# SCH_High_Voltage_Multipler_2022-07-10.net
KiCad netlist of a schematic drawn in EasyEDA
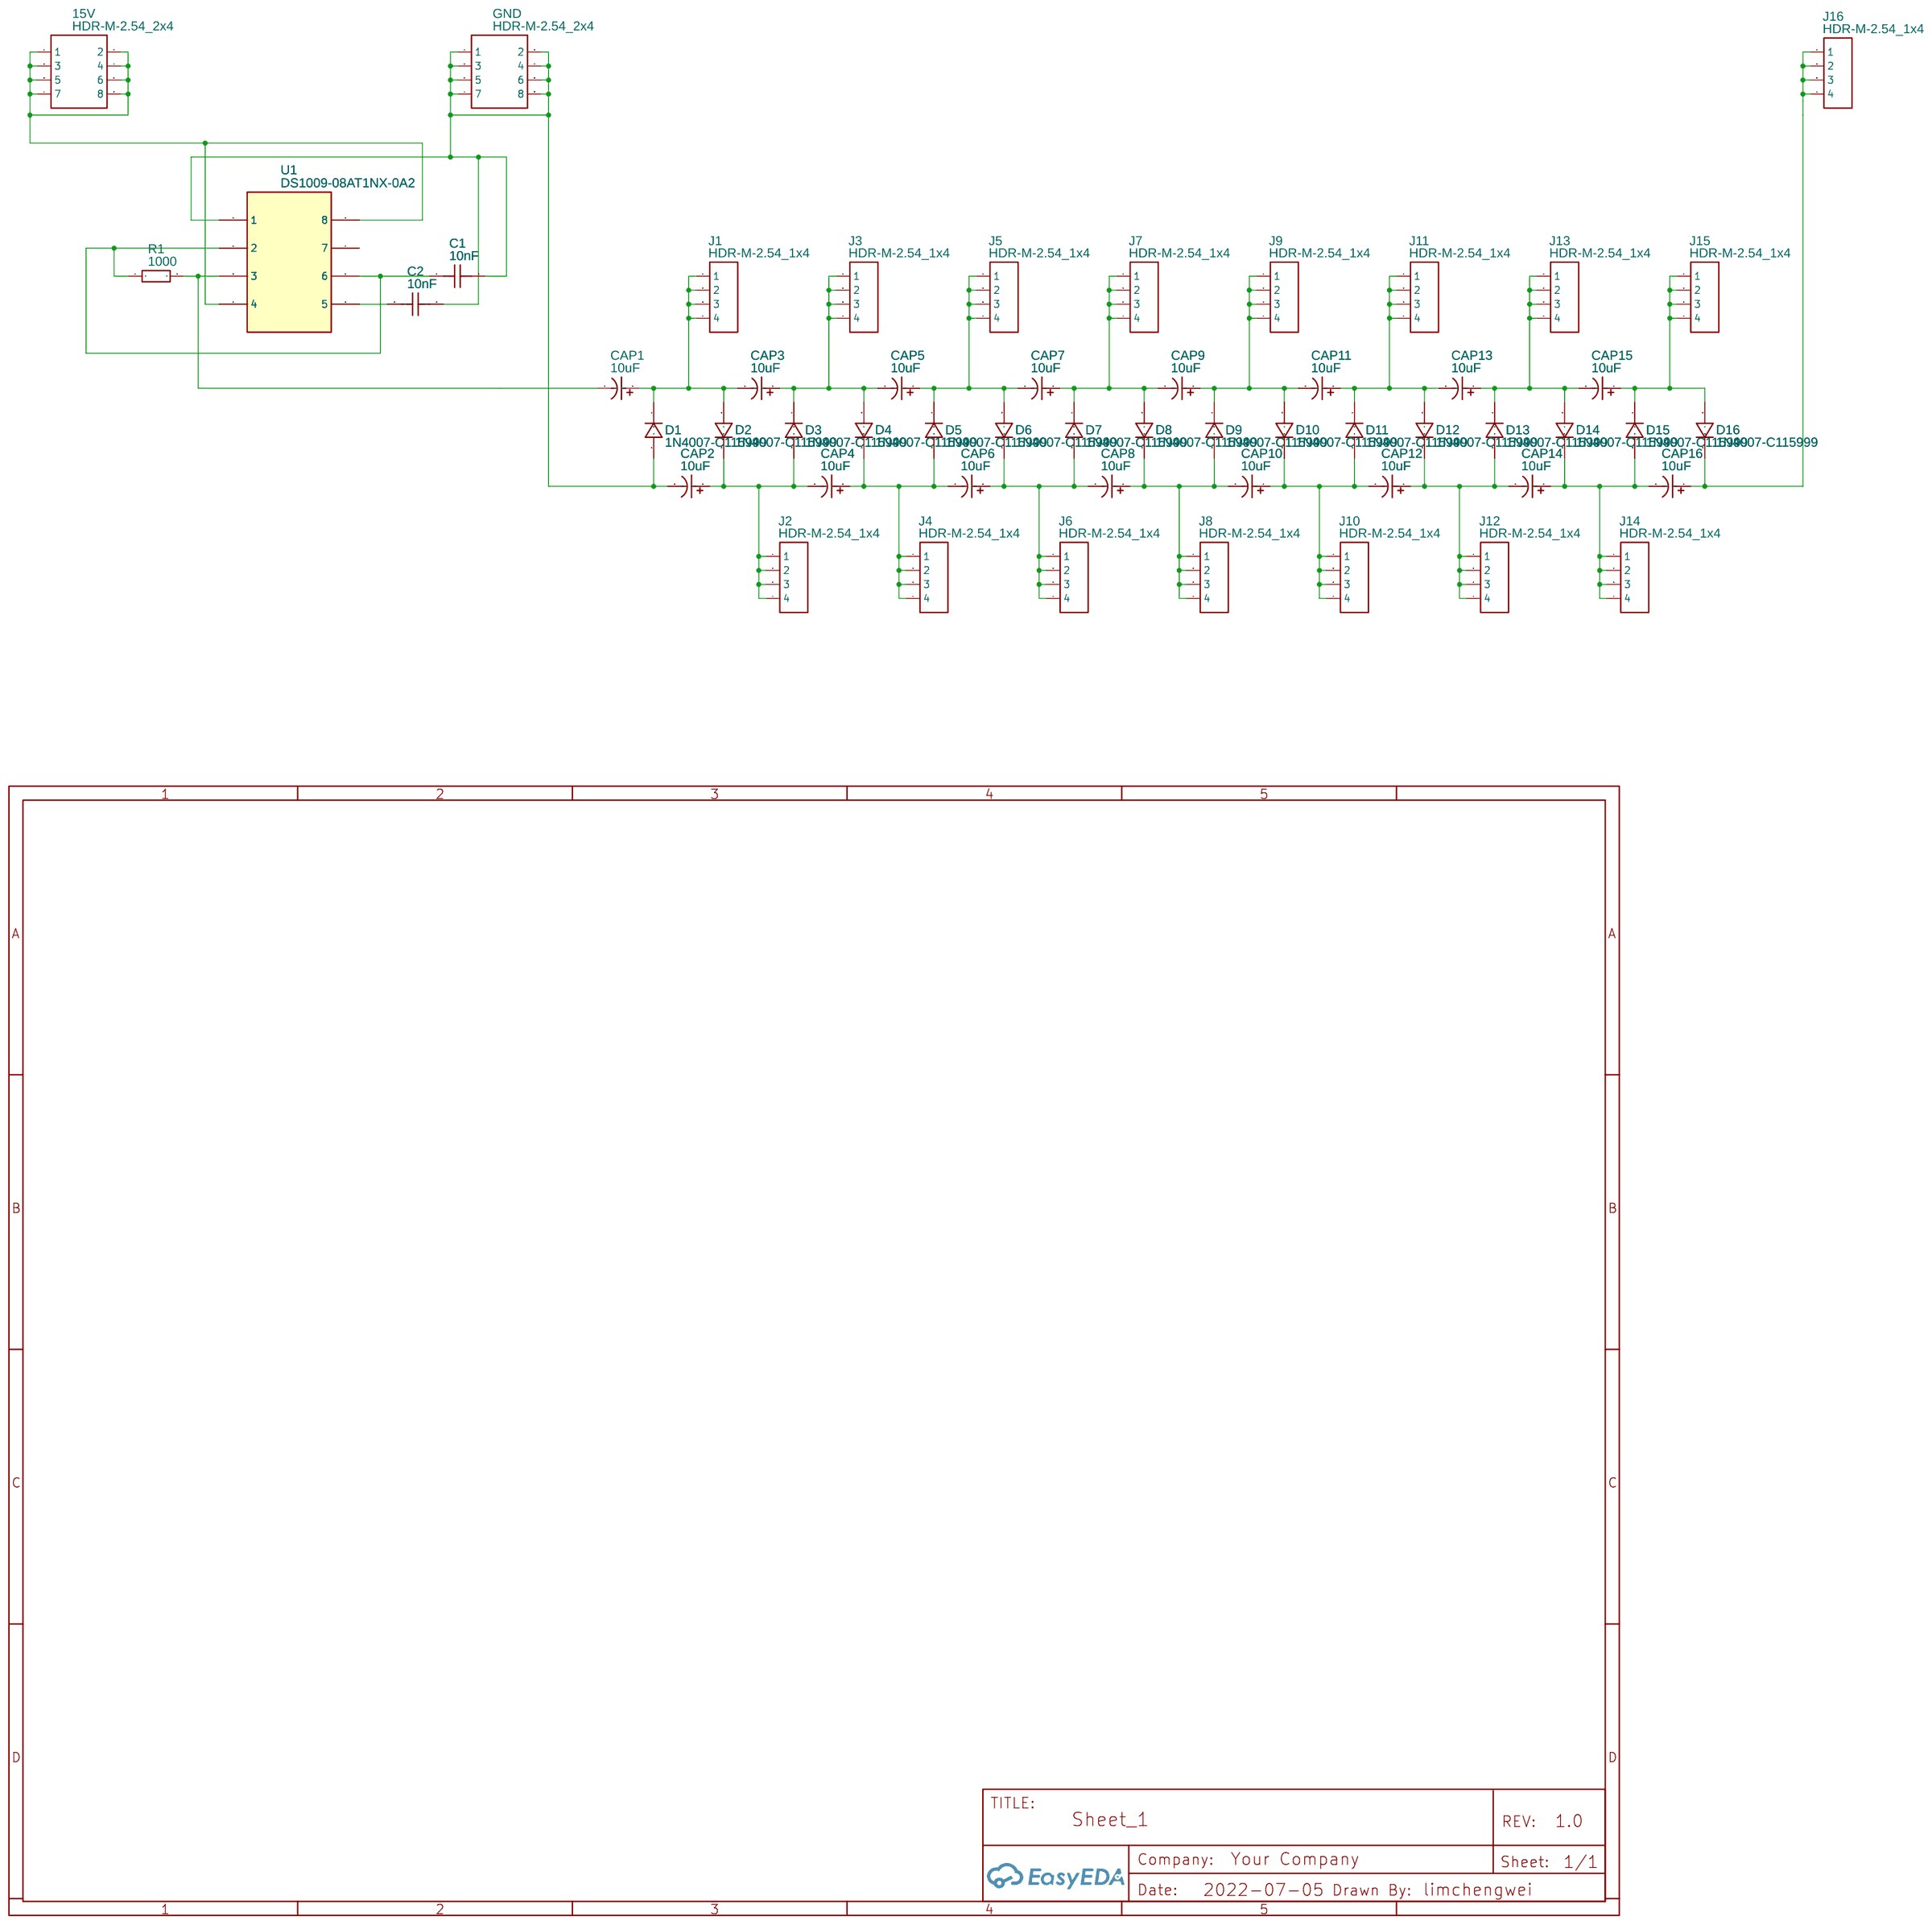
[diagram p0: schematic sheet]

(export (version "E")
  (design (tool "Eeschema 10.0.6"))
  (components
    (comp (ref "15V")
      (value "HDR-M-2.54_2x4")
      (fields (field (name "BOM_Supplier Part") "C58363"))
      (libsource (lib "") (part "HDR-M-2.54_2x4"))
    )
    (comp (ref "C1")
      (value "10nF")
      (fields
        (field (name "BOM_Manufacturer Part") "CC1H103MC76DB45A30S8")
        (field (name "BOM_Supplier Part") "C377837")
      )
      (libsource (lib "") (part "CC1H103MC76DB45A30S8"))
    )
    (comp (ref "C2")
      (value "10nF")
      (fields
        (field (name "BOM_Manufacturer Part") "CC1H103MC76DB45A30S8")
        (field (name "BOM_Supplier Part") "C377837")
      )
      (libsource (lib "") (part "CC1H103MC76DB45A30S8"))
    )
    (comp (ref "CAP1")
      (value "10uF")
      (fields
        (field (name "BOM_Manufacturer Part") "RL1E100MC110A00CV0")
        (field (name "BOM_Supplier Part") "C216293")
      )
      (libsource (lib "") (part "RL1E100MC110A00CV0"))
    )
    (comp (ref "CAP2")
      (value "10uF")
      (fields
        (field (name "BOM_Manufacturer Part") "RL1E100MC110A00CV0")
        (field (name "BOM_Supplier Part") "C216293")
      )
      (libsource (lib "") (part "RL1E100MC110A00CV0"))
    )
    (comp (ref "CAP3")
      (value "10uF")
      (fields
        (field (name "BOM_Manufacturer Part") "RL1E100MC110A00CV0")
        (field (name "BOM_Supplier Part") "C216293")
      )
      (libsource (lib "") (part "RL1E100MC110A00CV0"))
    )
    (comp (ref "CAP4")
      (value "10uF")
      (fields
        (field (name "BOM_Manufacturer Part") "RL1E100MC110A00CV0")
        (field (name "BOM_Supplier Part") "C216293")
      )
      (libsource (lib "") (part "RL1E100MC110A00CV0"))
    )
    (comp (ref "CAP5")
      (value "10uF")
      (fields
        (field (name "BOM_Manufacturer Part") "RL1E100MC110A00CV0")
        (field (name "BOM_Supplier Part") "C216293")
      )
      (libsource (lib "") (part "RL1E100MC110A00CV0"))
    )
    (comp (ref "CAP6")
      (value "10uF")
      (fields
        (field (name "BOM_Manufacturer Part") "RL1E100MC110A00CV0")
        (field (name "BOM_Supplier Part") "C216293")
      )
      (libsource (lib "") (part "RL1E100MC110A00CV0"))
    )
    (comp (ref "CAP7")
      (value "10uF")
      (fields
        (field (name "BOM_Manufacturer Part") "RL1E100MC110A00CV0")
        (field (name "BOM_Supplier Part") "C216293")
      )
      (libsource (lib "") (part "RL1E100MC110A00CV0"))
    )
    (comp (ref "CAP8")
      (value "10uF")
      (fields
        (field (name "BOM_Manufacturer Part") "RL1E100MC110A00CV0")
        (field (name "BOM_Supplier Part") "C216293")
      )
      (libsource (lib "") (part "RL1E100MC110A00CV0"))
    )
    (comp (ref "CAP9")
      (value "10uF")
      (fields
        (field (name "BOM_Manufacturer Part") "RL1E100MC110A00CV0")
        (field (name "BOM_Supplier Part") "C216293")
      )
      (libsource (lib "") (part "RL1E100MC110A00CV0"))
    )
    (comp (ref "CAP10")
      (value "10uF")
      (fields
        (field (name "BOM_Manufacturer Part") "RL1E100MC110A00CV0")
        (field (name "BOM_Supplier Part") "C216293")
      )
      (libsource (lib "") (part "RL1E100MC110A00CV0"))
    )
    (comp (ref "CAP11")
      (value "10uF")
      (fields
        (field (name "BOM_Manufacturer Part") "RL1E100MC110A00CV0")
        (field (name "BOM_Supplier Part") "C216293")
      )
      (libsource (lib "") (part "RL1E100MC110A00CV0"))
    )
    (comp (ref "CAP12")
      (value "10uF")
      (fields
        (field (name "BOM_Manufacturer Part") "RL1E100MC110A00CV0")
        (field (name "BOM_Supplier Part") "C216293")
      )
      (libsource (lib "") (part "RL1E100MC110A00CV0"))
    )
    (comp (ref "CAP13")
      (value "10uF")
      (fields
        (field (name "BOM_Manufacturer Part") "RL1E100MC110A00CV0")
        (field (name "BOM_Supplier Part") "C216293")
      )
      (libsource (lib "") (part "RL1E100MC110A00CV0"))
    )
    (comp (ref "CAP14")
      (value "10uF")
      (fields
        (field (name "BOM_Manufacturer Part") "RL1E100MC110A00CV0")
        (field (name "BOM_Supplier Part") "C216293")
      )
      (libsource (lib "") (part "RL1E100MC110A00CV0"))
    )
    (comp (ref "CAP15")
      (value "10uF")
      (fields
        (field (name "BOM_Manufacturer Part") "RL1E100MC110A00CV0")
        (field (name "BOM_Supplier Part") "C216293")
      )
      (libsource (lib "") (part "RL1E100MC110A00CV0"))
    )
    (comp (ref "CAP16")
      (value "10uF")
      (fields
        (field (name "BOM_Manufacturer Part") "RL1E100MC110A00CV0")
        (field (name "BOM_Supplier Part") "C216293")
      )
      (libsource (lib "") (part "RL1E100MC110A00CV0"))
    )
    (comp (ref "D1")
      (value "1N4007-C115999")
      (fields (field (name "BOM_Manufacturer Part") "1N4007") (field (name "BOM_Supplier Part") "C115999"))
      (libsource (lib "") (part "1N4007-C115999"))
    )
    (comp (ref "D2")
      (value "1N4007-C115999")
      (fields (field (name "BOM_Manufacturer Part") "1N4007") (field (name "BOM_Supplier Part") "C115999"))
      (libsource (lib "") (part "1N4007-C115999_1"))
    )
    (comp (ref "D3")
      (value "1N4007-C115999")
      (fields (field (name "BOM_Manufacturer Part") "1N4007") (field (name "BOM_Supplier Part") "C115999"))
      (libsource (lib "") (part "1N4007-C115999"))
    )
    (comp (ref "D4")
      (value "1N4007-C115999")
      (fields (field (name "BOM_Manufacturer Part") "1N4007") (field (name "BOM_Supplier Part") "C115999"))
      (libsource (lib "") (part "1N4007-C115999_1"))
    )
    (comp (ref "D5")
      (value "1N4007-C115999")
      (fields (field (name "BOM_Manufacturer Part") "1N4007") (field (name "BOM_Supplier Part") "C115999"))
      (libsource (lib "") (part "1N4007-C115999"))
    )
    (comp (ref "D6")
      (value "1N4007-C115999")
      (fields (field (name "BOM_Manufacturer Part") "1N4007") (field (name "BOM_Supplier Part") "C115999"))
      (libsource (lib "") (part "1N4007-C115999_1"))
    )
    (comp (ref "D7")
      (value "1N4007-C115999")
      (fields (field (name "BOM_Manufacturer Part") "1N4007") (field (name "BOM_Supplier Part") "C115999"))
      (libsource (lib "") (part "1N4007-C115999"))
    )
    (comp (ref "D8")
      (value "1N4007-C115999")
      (fields (field (name "BOM_Manufacturer Part") "1N4007") (field (name "BOM_Supplier Part") "C115999"))
      (libsource (lib "") (part "1N4007-C115999_1"))
    )
    (comp (ref "D9")
      (value "1N4007-C115999")
      (fields (field (name "BOM_Manufacturer Part") "1N4007") (field (name "BOM_Supplier Part") "C115999"))
      (libsource (lib "") (part "1N4007-C115999"))
    )
    (comp (ref "D10")
      (value "1N4007-C115999")
      (fields (field (name "BOM_Manufacturer Part") "1N4007") (field (name "BOM_Supplier Part") "C115999"))
      (libsource (lib "") (part "1N4007-C115999_1"))
    )
    (comp (ref "D11")
      (value "1N4007-C115999")
      (fields (field (name "BOM_Manufacturer Part") "1N4007") (field (name "BOM_Supplier Part") "C115999"))
      (libsource (lib "") (part "1N4007-C115999"))
    )
    (comp (ref "D12")
      (value "1N4007-C115999")
      (fields (field (name "BOM_Manufacturer Part") "1N4007") (field (name "BOM_Supplier Part") "C115999"))
      (libsource (lib "") (part "1N4007-C115999_1"))
    )
    (comp (ref "D13")
      (value "1N4007-C115999")
      (fields (field (name "BOM_Manufacturer Part") "1N4007") (field (name "BOM_Supplier Part") "C115999"))
      (libsource (lib "") (part "1N4007-C115999"))
    )
    (comp (ref "D14")
      (value "1N4007-C115999")
      (fields (field (name "BOM_Manufacturer Part") "1N4007") (field (name "BOM_Supplier Part") "C115999"))
      (libsource (lib "") (part "1N4007-C115999_1"))
    )
    (comp (ref "D15")
      (value "1N4007-C115999")
      (fields (field (name "BOM_Manufacturer Part") "1N4007") (field (name "BOM_Supplier Part") "C115999"))
      (libsource (lib "") (part "1N4007-C115999"))
    )
    (comp (ref "D16")
      (value "1N4007-C115999")
      (fields (field (name "BOM_Manufacturer Part") "1N4007") (field (name "BOM_Supplier Part") "C115999"))
      (libsource (lib "") (part "1N4007-C115999_1"))
    )
    (comp (ref "GND")
      (value "HDR-M-2.54_2x4")
      (fields (field (name "BOM_Supplier Part") "C58363"))
      (libsource (lib "") (part "HDR-M-2.54_2x4_1"))
    )
    (comp (ref "J1")
      (value "HDR-M-2.54_1x4")
      (fields (field (name "BOM_Supplier Part") "C124378"))
      (libsource (lib "") (part "HDR-M-2.54_1x4"))
    )
    (comp (ref "J2")
      (value "HDR-M-2.54_1x4")
      (fields (field (name "BOM_Supplier Part") "C124378"))
      (libsource (lib "") (part "HDR-M-2.54_1x4"))
    )
    (comp (ref "J3")
      (value "HDR-M-2.54_1x4")
      (fields (field (name "BOM_Supplier Part") "C124378"))
      (libsource (lib "") (part "HDR-M-2.54_1x4"))
    )
    (comp (ref "J4")
      (value "HDR-M-2.54_1x4")
      (fields (field (name "BOM_Supplier Part") "C124378"))
      (libsource (lib "") (part "HDR-M-2.54_1x4"))
    )
    (comp (ref "J5")
      (value "HDR-M-2.54_1x4")
      (fields (field (name "BOM_Supplier Part") "C124378"))
      (libsource (lib "") (part "HDR-M-2.54_1x4"))
    )
    (comp (ref "J6")
      (value "HDR-M-2.54_1x4")
      (fields (field (name "BOM_Supplier Part") "C124378"))
      (libsource (lib "") (part "HDR-M-2.54_1x4"))
    )
    (comp (ref "J7")
      (value "HDR-M-2.54_1x4")
      (fields (field (name "BOM_Supplier Part") "C124378"))
      (libsource (lib "") (part "HDR-M-2.54_1x4"))
    )
    (comp (ref "J8")
      (value "HDR-M-2.54_1x4")
      (fields (field (name "BOM_Supplier Part") "C124378"))
      (libsource (lib "") (part "HDR-M-2.54_1x4"))
    )
    (comp (ref "J9")
      (value "HDR-M-2.54_1x4")
      (fields (field (name "BOM_Supplier Part") "C124378"))
      (libsource (lib "") (part "HDR-M-2.54_1x4"))
    )
    (comp (ref "J10")
      (value "HDR-M-2.54_1x4")
      (fields (field (name "BOM_Supplier Part") "C124378"))
      (libsource (lib "") (part "HDR-M-2.54_1x4"))
    )
    (comp (ref "J11")
      (value "HDR-M-2.54_1x4")
      (fields (field (name "BOM_Supplier Part") "C124378"))
      (libsource (lib "") (part "HDR-M-2.54_1x4"))
    )
    (comp (ref "J12")
      (value "HDR-M-2.54_1x4")
      (fields (field (name "BOM_Supplier Part") "C124378"))
      (libsource (lib "") (part "HDR-M-2.54_1x4"))
    )
    (comp (ref "J13")
      (value "HDR-M-2.54_1x4")
      (fields (field (name "BOM_Supplier Part") "C124378"))
      (libsource (lib "") (part "HDR-M-2.54_1x4"))
    )
    (comp (ref "J14")
      (value "HDR-M-2.54_1x4")
      (fields (field (name "BOM_Supplier Part") "C124378"))
      (libsource (lib "") (part "HDR-M-2.54_1x4"))
    )
    (comp (ref "J15")
      (value "HDR-M-2.54_1x4")
      (fields (field (name "BOM_Supplier Part") "C124378"))
      (libsource (lib "") (part "HDR-M-2.54_1x4"))
    )
    (comp (ref "J16")
      (value "HDR-M-2.54_1x4")
      (fields (field (name "BOM_Supplier Part") "C124378"))
      (libsource (lib "") (part "HDR-M-2.54_1x4"))
    )
    (comp (ref "R1")
      (value "1000")
      (fields (field (name "BOM_Supplier Part") "C119312"))
      (libsource (lib "") (part "MF1/4W-300Ω±1% T52"))
    )
    (comp (ref "U1")
      (value "DS1009-08AT1NX-0A2")
      (fields (field (name "BOM_Supplier Part") "C72124"))
      (libsource (lib "") (part "DS1009-08AT1NX-0A2"))
    )
  )
  (nets
    (net (code "1") (name "Net-(15V-Pad1)") (class "Default")
      (node (ref "15V") (pin "1") (pinfunction "1_1") (pintype "unspecified"))
      (node (ref "15V") (pin "2") (pinfunction "2_2") (pintype "unspecified"))
      (node (ref "15V") (pin "3") (pinfunction "3_3") (pintype "unspecified"))
      (node (ref "15V") (pin "4") (pinfunction "4_4") (pintype "unspecified"))
      (node (ref "15V") (pin "5") (pinfunction "5_5") (pintype "unspecified"))
      (node (ref "15V") (pin "6") (pinfunction "6_6") (pintype "unspecified"))
      (node (ref "15V") (pin "7") (pinfunction "7_7") (pintype "unspecified"))
      (node (ref "15V") (pin "8") (pinfunction "8_8") (pintype "unspecified"))
      (node (ref "U1") (pin "4") (pinfunction "4_4") (pintype "input"))
      (node (ref "U1") (pin "8") (pinfunction "8_8") (pintype "input"))
    )
    (net (code "2") (name "Net-(C1-Pad1)") (class "Default")
      (node (ref "C1") (pin "1") (pinfunction "1_1") (pintype "unspecified"))
      (node (ref "R1") (pin "1") (pinfunction "1_1") (pintype "unspecified"))
      (node (ref "U1") (pin "2") (pinfunction "2_2") (pintype "input"))
      (node (ref "U1") (pin "6") (pinfunction "6_6") (pintype "input"))
    )
    (net (code "3") (name "Net-(C2-Pad1)") (class "Default")
      (node (ref "C2") (pin "1") (pinfunction "1_1") (pintype "unspecified"))
      (node (ref "U1") (pin "5") (pinfunction "5_5") (pintype "input"))
    )
    (net (code "4") (name "Net-(CAP1-Pad2)") (class "Default")
      (node (ref "CAP1") (pin "2") (pinfunction "2_2") (pintype "input"))
      (node (ref "R1") (pin "2") (pinfunction "2_2") (pintype "unspecified"))
      (node (ref "U1") (pin "3") (pinfunction "3_3") (pintype "input"))
    )
    (net (code "5") (name "Net-(D1-A)") (class "Default")
      (node (ref "C1") (pin "2") (pinfunction "2_2") (pintype "unspecified"))
      (node (ref "C2") (pin "2") (pinfunction "2_2") (pintype "unspecified"))
      (node (ref "CAP2") (pin "2") (pinfunction "2_2") (pintype "input"))
      (node (ref "D1") (pin "2") (pinfunction "A_2") (pintype "unspecified"))
      (node (ref "GND") (pin "1") (pinfunction "1_1") (pintype "unspecified"))
      (node (ref "GND") (pin "2") (pinfunction "2_2") (pintype "unspecified"))
      (node (ref "GND") (pin "3") (pinfunction "3_3") (pintype "unspecified"))
      (node (ref "GND") (pin "4") (pinfunction "4_4") (pintype "unspecified"))
      (node (ref "GND") (pin "5") (pinfunction "5_5") (pintype "unspecified"))
      (node (ref "GND") (pin "6") (pinfunction "6_6") (pintype "unspecified"))
      (node (ref "GND") (pin "7") (pinfunction "7_7") (pintype "unspecified"))
      (node (ref "GND") (pin "8") (pinfunction "8_8") (pintype "unspecified"))
      (node (ref "U1") (pin "1") (pinfunction "1_1") (pintype "input"))
    )
    (net (code "6") (name "Net-(D1-C)") (class "Default")
      (node (ref "CAP1") (pin "1") (pinfunction "1_1") (pintype "input"))
      (node (ref "CAP3") (pin "2") (pinfunction "2_2") (pintype "input"))
      (node (ref "D1") (pin "1") (pinfunction "C_1") (pintype "unspecified"))
      (node (ref "D2") (pin "2") (pinfunction "A_2") (pintype "unspecified"))
      (node (ref "J1") (pin "1") (pinfunction "1_1") (pintype "unspecified"))
      (node (ref "J1") (pin "2") (pinfunction "2_2") (pintype "unspecified"))
      (node (ref "J1") (pin "3") (pinfunction "3_3") (pintype "unspecified"))
      (node (ref "J1") (pin "4") (pinfunction "4_4") (pintype "unspecified"))
    )
    (net (code "7") (name "Net-(D2-C)") (class "Default")
      (node (ref "CAP2") (pin "1") (pinfunction "1_1") (pintype "input"))
      (node (ref "CAP4") (pin "2") (pinfunction "2_2") (pintype "input"))
      (node (ref "D2") (pin "1") (pinfunction "C_1") (pintype "unspecified"))
      (node (ref "D3") (pin "2") (pinfunction "A_2") (pintype "unspecified"))
      (node (ref "J2") (pin "1") (pinfunction "1_1") (pintype "unspecified"))
      (node (ref "J2") (pin "2") (pinfunction "2_2") (pintype "unspecified"))
      (node (ref "J2") (pin "3") (pinfunction "3_3") (pintype "unspecified"))
      (node (ref "J2") (pin "4") (pinfunction "4_4") (pintype "unspecified"))
    )
    (net (code "8") (name "Net-(D3-C)") (class "Default")
      (node (ref "CAP3") (pin "1") (pinfunction "1_1") (pintype "input"))
      (node (ref "CAP5") (pin "2") (pinfunction "2_2") (pintype "input"))
      (node (ref "D3") (pin "1") (pinfunction "C_1") (pintype "unspecified"))
      (node (ref "D4") (pin "2") (pinfunction "A_2") (pintype "unspecified"))
      (node (ref "J3") (pin "1") (pinfunction "1_1") (pintype "unspecified"))
      (node (ref "J3") (pin "2") (pinfunction "2_2") (pintype "unspecified"))
      (node (ref "J3") (pin "3") (pinfunction "3_3") (pintype "unspecified"))
      (node (ref "J3") (pin "4") (pinfunction "4_4") (pintype "unspecified"))
    )
    (net (code "9") (name "Net-(D4-C)") (class "Default")
      (node (ref "CAP4") (pin "1") (pinfunction "1_1") (pintype "input"))
      (node (ref "CAP6") (pin "2") (pinfunction "2_2") (pintype "input"))
      (node (ref "D4") (pin "1") (pinfunction "C_1") (pintype "unspecified"))
      (node (ref "D5") (pin "2") (pinfunction "A_2") (pintype "unspecified"))
      (node (ref "J4") (pin "1") (pinfunction "1_1") (pintype "unspecified"))
      (node (ref "J4") (pin "2") (pinfunction "2_2") (pintype "unspecified"))
      (node (ref "J4") (pin "3") (pinfunction "3_3") (pintype "unspecified"))
      (node (ref "J4") (pin "4") (pinfunction "4_4") (pintype "unspecified"))
    )
    (net (code "10") (name "Net-(D5-C)") (class "Default")
      (node (ref "CAP5") (pin "1") (pinfunction "1_1") (pintype "input"))
      (node (ref "CAP7") (pin "2") (pinfunction "2_2") (pintype "input"))
      (node (ref "D5") (pin "1") (pinfunction "C_1") (pintype "unspecified"))
      (node (ref "D6") (pin "2") (pinfunction "A_2") (pintype "unspecified"))
      (node (ref "J5") (pin "1") (pinfunction "1_1") (pintype "unspecified"))
      (node (ref "J5") (pin "2") (pinfunction "2_2") (pintype "unspecified"))
      (node (ref "J5") (pin "3") (pinfunction "3_3") (pintype "unspecified"))
      (node (ref "J5") (pin "4") (pinfunction "4_4") (pintype "unspecified"))
    )
    (net (code "11") (name "Net-(D6-C)") (class "Default")
      (node (ref "CAP6") (pin "1") (pinfunction "1_1") (pintype "input"))
      (node (ref "CAP8") (pin "2") (pinfunction "2_2") (pintype "input"))
      (node (ref "D6") (pin "1") (pinfunction "C_1") (pintype "unspecified"))
      (node (ref "D7") (pin "2") (pinfunction "A_2") (pintype "unspecified"))
      (node (ref "J6") (pin "1") (pinfunction "1_1") (pintype "unspecified"))
      (node (ref "J6") (pin "2") (pinfunction "2_2") (pintype "unspecified"))
      (node (ref "J6") (pin "3") (pinfunction "3_3") (pintype "unspecified"))
      (node (ref "J6") (pin "4") (pinfunction "4_4") (pintype "unspecified"))
    )
    (net (code "12") (name "Net-(D7-C)") (class "Default")
      (node (ref "CAP7") (pin "1") (pinfunction "1_1") (pintype "input"))
      (node (ref "CAP9") (pin "2") (pinfunction "2_2") (pintype "input"))
      (node (ref "D7") (pin "1") (pinfunction "C_1") (pintype "unspecified"))
      (node (ref "D8") (pin "2") (pinfunction "A_2") (pintype "unspecified"))
      (node (ref "J7") (pin "1") (pinfunction "1_1") (pintype "unspecified"))
      (node (ref "J7") (pin "2") (pinfunction "2_2") (pintype "unspecified"))
      (node (ref "J7") (pin "3") (pinfunction "3_3") (pintype "unspecified"))
      (node (ref "J7") (pin "4") (pinfunction "4_4") (pintype "unspecified"))
    )
    (net (code "13") (name "Net-(D8-C)") (class "Default")
      (node (ref "CAP10") (pin "2") (pinfunction "2_2") (pintype "input"))
      (node (ref "CAP8") (pin "1") (pinfunction "1_1") (pintype "input"))
      (node (ref "D8") (pin "1") (pinfunction "C_1") (pintype "unspecified"))
      (node (ref "D9") (pin "2") (pinfunction "A_2") (pintype "unspecified"))
      (node (ref "J8") (pin "1") (pinfunction "1_1") (pintype "unspecified"))
      (node (ref "J8") (pin "2") (pinfunction "2_2") (pintype "unspecified"))
      (node (ref "J8") (pin "3") (pinfunction "3_3") (pintype "unspecified"))
      (node (ref "J8") (pin "4") (pinfunction "4_4") (pintype "unspecified"))
    )
    (net (code "14") (name "Net-(D10-A)") (class "Default")
      (node (ref "CAP11") (pin "2") (pinfunction "2_2") (pintype "input"))
      (node (ref "CAP9") (pin "1") (pinfunction "1_1") (pintype "input"))
      (node (ref "D10") (pin "2") (pinfunction "A_2") (pintype "unspecified"))
      (node (ref "D9") (pin "1") (pinfunction "C_1") (pintype "unspecified"))
      (node (ref "J9") (pin "1") (pinfunction "1_1") (pintype "unspecified"))
      (node (ref "J9") (pin "2") (pinfunction "2_2") (pintype "unspecified"))
      (node (ref "J9") (pin "3") (pinfunction "3_3") (pintype "unspecified"))
      (node (ref "J9") (pin "4") (pinfunction "4_4") (pintype "unspecified"))
    )
    (net (code "15") (name "Net-(D10-C)") (class "Default")
      (node (ref "CAP10") (pin "1") (pinfunction "1_1") (pintype "input"))
      (node (ref "CAP12") (pin "2") (pinfunction "2_2") (pintype "input"))
      (node (ref "D10") (pin "1") (pinfunction "C_1") (pintype "unspecified"))
      (node (ref "D11") (pin "2") (pinfunction "A_2") (pintype "unspecified"))
      (node (ref "J10") (pin "1") (pinfunction "1_1") (pintype "unspecified"))
      (node (ref "J10") (pin "2") (pinfunction "2_2") (pintype "unspecified"))
      (node (ref "J10") (pin "3") (pinfunction "3_3") (pintype "unspecified"))
      (node (ref "J10") (pin "4") (pinfunction "4_4") (pintype "unspecified"))
    )
    (net (code "16") (name "Net-(D11-C)") (class "Default")
      (node (ref "CAP11") (pin "1") (pinfunction "1_1") (pintype "input"))
      (node (ref "CAP13") (pin "2") (pinfunction "2_2") (pintype "input"))
      (node (ref "D11") (pin "1") (pinfunction "C_1") (pintype "unspecified"))
      (node (ref "D12") (pin "2") (pinfunction "A_2") (pintype "unspecified"))
      (node (ref "J11") (pin "1") (pinfunction "1_1") (pintype "unspecified"))
      (node (ref "J11") (pin "2") (pinfunction "2_2") (pintype "unspecified"))
      (node (ref "J11") (pin "3") (pinfunction "3_3") (pintype "unspecified"))
      (node (ref "J11") (pin "4") (pinfunction "4_4") (pintype "unspecified"))
    )
    (net (code "17") (name "Net-(D12-C)") (class "Default")
      (node (ref "CAP12") (pin "1") (pinfunction "1_1") (pintype "input"))
      (node (ref "CAP14") (pin "2") (pinfunction "2_2") (pintype "input"))
      (node (ref "D12") (pin "1") (pinfunction "C_1") (pintype "unspecified"))
      (node (ref "D13") (pin "2") (pinfunction "A_2") (pintype "unspecified"))
      (node (ref "J12") (pin "1") (pinfunction "1_1") (pintype "unspecified"))
      (node (ref "J12") (pin "2") (pinfunction "2_2") (pintype "unspecified"))
      (node (ref "J12") (pin "3") (pinfunction "3_3") (pintype "unspecified"))
      (node (ref "J12") (pin "4") (pinfunction "4_4") (pintype "unspecified"))
    )
    (net (code "18") (name "Net-(D13-C)") (class "Default")
      (node (ref "CAP13") (pin "1") (pinfunction "1_1") (pintype "input"))
      (node (ref "CAP15") (pin "2") (pinfunction "2_2") (pintype "input"))
      (node (ref "D13") (pin "1") (pinfunction "C_1") (pintype "unspecified"))
      (node (ref "D14") (pin "2") (pinfunction "A_2") (pintype "unspecified"))
      (node (ref "J13") (pin "1") (pinfunction "1_1") (pintype "unspecified"))
      (node (ref "J13") (pin "2") (pinfunction "2_2") (pintype "unspecified"))
      (node (ref "J13") (pin "3") (pinfunction "3_3") (pintype "unspecified"))
      (node (ref "J13") (pin "4") (pinfunction "4_4") (pintype "unspecified"))
    )
    (net (code "19") (name "Net-(D14-C)") (class "Default")
      (node (ref "CAP14") (pin "1") (pinfunction "1_1") (pintype "input"))
      (node (ref "CAP16") (pin "2") (pinfunction "2_2") (pintype "input"))
      (node (ref "D14") (pin "1") (pinfunction "C_1") (pintype "unspecified"))
      (node (ref "D15") (pin "2") (pinfunction "A_2") (pintype "unspecified"))
      (node (ref "J14") (pin "1") (pinfunction "1_1") (pintype "unspecified"))
      (node (ref "J14") (pin "2") (pinfunction "2_2") (pintype "unspecified"))
      (node (ref "J14") (pin "3") (pinfunction "3_3") (pintype "unspecified"))
      (node (ref "J14") (pin "4") (pinfunction "4_4") (pintype "unspecified"))
    )
    (net (code "20") (name "Net-(D15-C)") (class "Default")
      (node (ref "CAP15") (pin "1") (pinfunction "1_1") (pintype "input"))
      (node (ref "D15") (pin "1") (pinfunction "C_1") (pintype "unspecified"))
      (node (ref "D16") (pin "2") (pinfunction "A_2") (pintype "unspecified"))
      (node (ref "J15") (pin "1") (pinfunction "1_1") (pintype "unspecified"))
      (node (ref "J15") (pin "2") (pinfunction "2_2") (pintype "unspecified"))
      (node (ref "J15") (pin "3") (pinfunction "3_3") (pintype "unspecified"))
      (node (ref "J15") (pin "4") (pinfunction "4_4") (pintype "unspecified"))
    )
    (net (code "21") (name "Net-(D16-C)") (class "Default")
      (node (ref "CAP16") (pin "1") (pinfunction "1_1") (pintype "input"))
      (node (ref "D16") (pin "1") (pinfunction "C_1") (pintype "unspecified"))
      (node (ref "J16") (pin "1") (pinfunction "1_1") (pintype "unspecified"))
      (node (ref "J16") (pin "2") (pinfunction "2_2") (pintype "unspecified"))
      (node (ref "J16") (pin "3") (pinfunction "3_3") (pintype "unspecified"))
      (node (ref "J16") (pin "4") (pinfunction "4_4") (pintype "unspecified"))
    )
    (net (code "22") (name "unconnected-(U1-Pad7)") (class "Default")
      (node (ref "U1") (pin "7") (pinfunction "7_7") (pintype "input"))
    )
  )
)
